# ARDUINO_MSP430F2370.net
KiCad netlist of a schematic drawn in Altium Designer
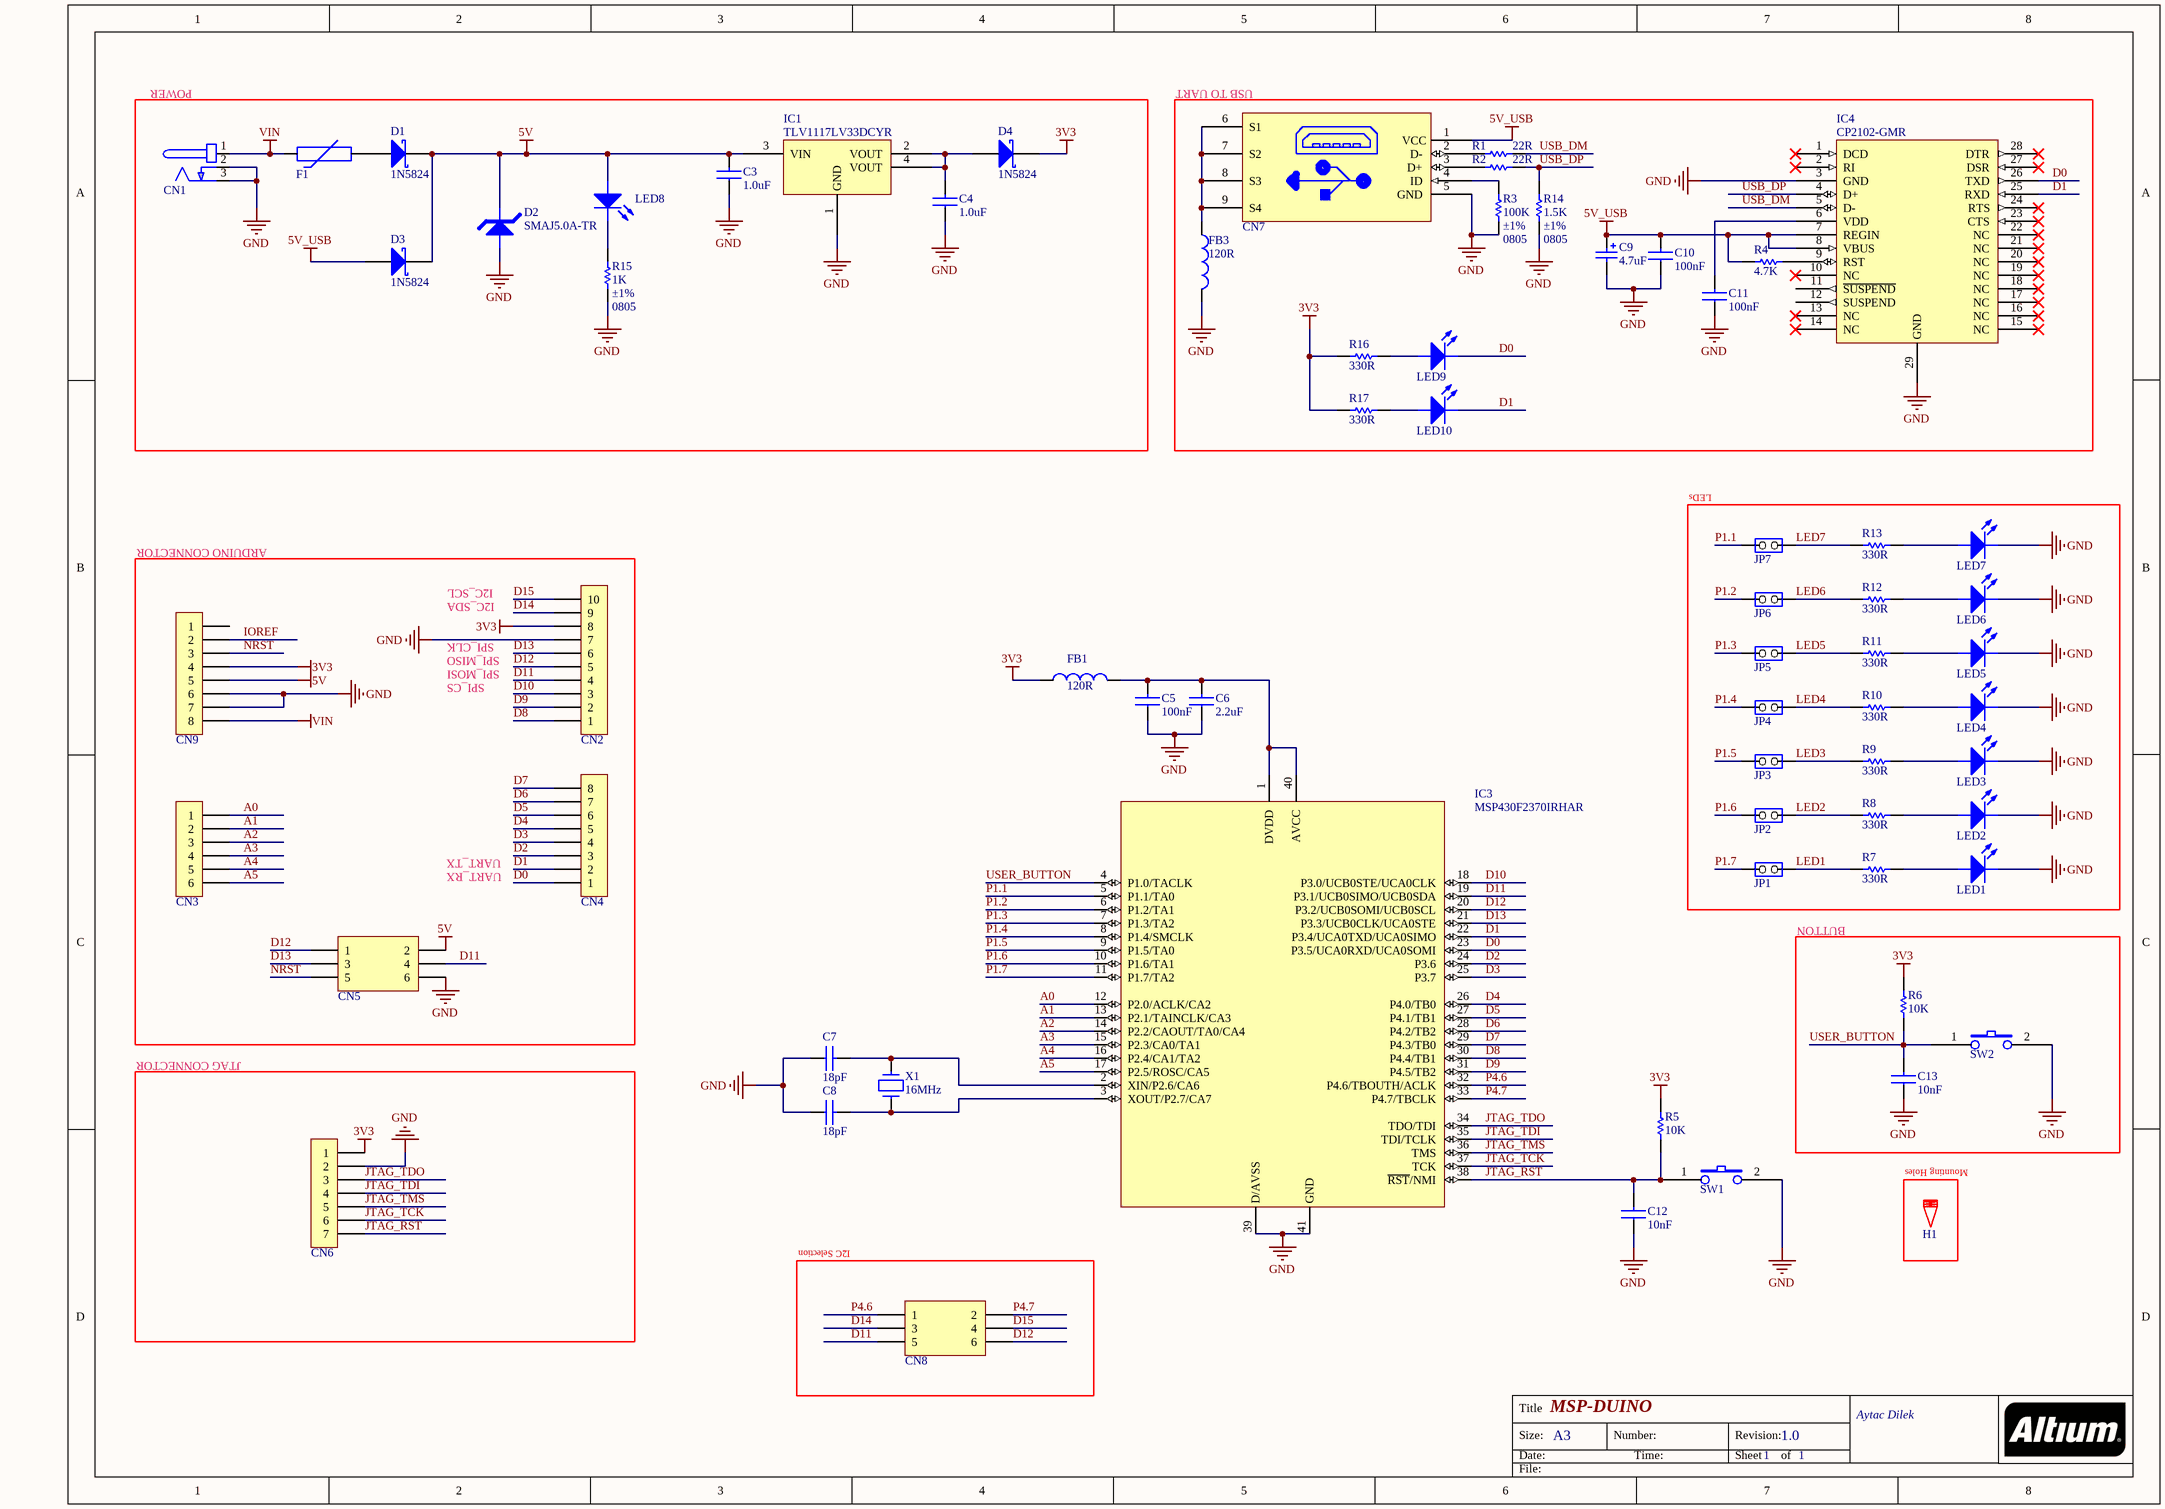
[diagram p0: ARDUINO_MSP430F2370.SchDoc]

(export (version "E")
  (design (tool "Eeschema 10.0.6"))
  (components
    (comp (ref "C3")
      (value "1.0uF")
      (footprint "CAPC2012X100N_EIA0805")
      (description "CAP CER 1UF 25V 10% X7R 0603")
      (fields (field (name "PART NUMBER") "SCAP00310053") (field (name "TOLERANCE") "±10%"))
      (libsource (lib "ComponentDatabase") (part "CAP_NP"))
    )
    (comp (ref "C4")
      (value "1.0uF")
      (footprint "CAPC2012X100N_EIA0805")
      (description "CAP CER 1UF 25V 10% X7R 0603")
      (fields (field (name "PART NUMBER") "SCAP00310053") (field (name "TOLERANCE") "±10%"))
      (libsource (lib "ComponentDatabase") (part "CAP_NP"))
    )
    (comp (ref "C5")
      (value "100nF")
      (footprint "CAPC2012X100N_EIA0805")
      (description "CAP CER 0.1UF 50V 10% X7R 0603")
      (fields (field (name "PART NUMBER") "SCAP00310048") (field (name "TOLERANCE") "±10%"))
      (libsource (lib "ComponentDatabase") (part "CAP_NP"))
    )
    (comp (ref "C6")
      (value "2.2uF")
      (footprint "CAPC2012X100N_EIA0805")
      (description "CAP CER 2.2UF 16V X5R 0805")
      (fields (field (name "PART NUMBER") "SCAP00300098") (field (name "TOLERANCE") "±10%"))
      (libsource (lib "ComponentDatabase") (part "CAP_NP"))
    )
    (comp (ref "C7")
      (value "18pF")
      (footprint "CAPC2012X100N_EIA0805")
      (description "CAP CER 18PF 50V 5% NP0 0603")
      (fields (field (name "PART NUMBER") "SCAP00310014") (field (name "TOLERANCE") "±5%"))
      (libsource (lib "ComponentDatabase") (part "CAP_NP"))
    )
    (comp (ref "C8")
      (value "18pF")
      (footprint "CAPC2012X100N_EIA0805")
      (description "CAP CER 18PF 50V 5% NP0 0603")
      (fields (field (name "PART NUMBER") "SCAP00310014") (field (name "TOLERANCE") "±5%"))
      (libsource (lib "ComponentDatabase") (part "CAP_NP"))
    )
    (comp (ref "C9")
      (value "4.7uF")
      (footprint "CAPMP3216X16N_EIA-1206_CASE-A")
      (description "CAP TANT 4.7UF 16V 10% 1206")
      (fields (field (name "PART NUMBER") "SCAP00367") (field (name "TOLERANCE") "±10%"))
      (libsource (lib "ComponentDatabase") (part "CAP_P"))
    )
    (comp (ref "C10")
      (value "100nF")
      (footprint "CAPC2012X100N_EIA0805")
      (description "CAP CER 0.1UF 50V 10% X7R 0603")
      (fields (field (name "PART NUMBER") "SCAP00310048") (field (name "TOLERANCE") "±10%"))
      (libsource (lib "ComponentDatabase") (part "CAP_NP"))
    )
    (comp (ref "C11")
      (value "100nF")
      (footprint "CAPC2012X100N_EIA0805")
      (description "CAP CER 0.1UF 50V 10% X7R 0603")
      (fields (field (name "PART NUMBER") "SCAP00310048") (field (name "TOLERANCE") "±10%"))
      (libsource (lib "ComponentDatabase") (part "CAP_NP"))
    )
    (comp (ref "C12")
      (value "10nF")
      (footprint "CAPC2012X100N_EIA0805")
      (description "CAP CER 10000PF 50V 10% X7R 0603")
      (fields (field (name "PART NUMBER") "SCAP00310042") (field (name "TOLERANCE") "±10%"))
      (libsource (lib "ComponentDatabase") (part "CAP_NP"))
    )
    (comp (ref "C13")
      (value "10nF")
      (footprint "CAPC2012X100N_EIA0805")
      (description "CAP CER 10000PF 50V 10% X7R 0603")
      (fields (field (name "PART NUMBER") "SCAP00310042") (field (name "TOLERANCE") "±10%"))
      (libsource (lib "ComponentDatabase") (part "CAP_NP"))
    )
    (comp (ref "CN1")
      (value "DC_JACK")
      (footprint "DC_JACK")
      (description "CONN POWER JACK MALE 2.5MM CLSD")
      (fields (field (name "PART NUMBER") "SCON00027") (field (name "VOLTAGE") "24VDC"))
      (libsource (lib "ComponentDatabase") (part "DC_JACK"))
    )
    (comp (ref "CN2")
      (value "HDR_1X10")
      (footprint "HDRFV10W70P254_1X10_2540X254X1118P")
      (description "CONN ARDUINO HEADER .0100\" 10POS")
      (fields (field (name "PART NUMBER") "SCON00126") (field (name "MANUFACTURER") "Sparkfun"))
      (libsource (lib "ComponentDatabase") (part "HDR_1X10"))
    )
    (comp (ref "CN3")
      (value "HDR_1X6")
      (footprint "HDRFV6W70P254_1X6_1524X254X1118P")
      (description "CONN ARDUINO HEADER .0100\" 6POS")
      (fields (field (name "PART NUMBER") "SCON00124") (field (name "MANUFACTURER") "Sparkfun"))
      (libsource (lib "ComponentDatabase") (part "HDR_1X6"))
    )
    (comp (ref "CN4")
      (value "HDR_1X8")
      (footprint "HDRFV8W70P254_1X8_2032X254X1118P")
      (description "CONN ARDUINO HEADER .0100\" 8POS")
      (fields (field (name "PART NUMBER") "SCON00125") (field (name "MANUFACTURER") "Sparkfun"))
      (libsource (lib "") (part "HDR_1X8_1"))
    )
    (comp (ref "CN5")
      (value "HDR_2X3")
      (footprint "HDRV6W64P254_2X3_762X508X600P")
      (description "CONN HEADER FMALE 6PS .1\" DL TIN")
      (fields
        (field (name "PART NUMBER") "SCON00128")
        (field (name "MANUFACTURER") "Sullins Connector Solutions")
      )
      (libsource (lib "ComponentDatabase") (part "HDR_2X3"))
    )
    (comp (ref "CN6")
      (value "HDR_1X7")
      (footprint "HDRFV7W70P254_1X7_1778X254X1118P")
      (description "CONN ARDUINO HEADER .0100\" 7POS")
      (fields (field (name "PART NUMBER") "SCON00129") (field (name "MANUFACTURER") "Wurth Electronics Inc"))
      (libsource (lib "ComponentDatabase") (part "HDR_1X7"))
    )
    (comp (ref "CN7")
      (value "USB_MINI_TYPE_B")
      (footprint "OST_USB-M26FTR")
      (description "CONN USB MINI B R/A SMD")
      (fields (field (name "PART NUMBER") "SCON00017") (field (name "MANUFACTURER") "On Shore Technology"))
      (libsource (lib "ComponentDatabase") (part "USB_MINI_TYPE_B"))
    )
    (comp (ref "CN8")
      (value "HDR_2X3")
      (footprint "HDRV6W64P254_2X3_762X508X600P")
      (description "CONN HEADER FMALE 6PS .1\" DL TIN")
      (fields
        (field (name "PART NUMBER") "SCON00128")
        (field (name "MANUFACTURER") "Sullins Connector Solutions")
      )
      (libsource (lib "ComponentDatabase") (part "HDR_2X3"))
    )
    (comp (ref "CN9")
      (value "HDR_1X8")
      (footprint "HDRFV8W70P254_1X8_2032X254X1118P")
      (description "CONN ARDUINO HEADER .0100\" 8POS")
      (fields (field (name "PART NUMBER") "SCON00125") (field (name "MANUFACTURER") "Sparkfun"))
      (libsource (lib "ComponentDatabase") (part "HDR_1X8"))
    )
    (comp (ref "D1")
      (value "1N5824")
      (footprint "DIOM4436X24N_DO-214AA_SMB")
      (description "DIODE SCHOTTKY 5A 40V SMA")
      (fields (field (name "PART NUMBER") "SSEM00019") (field (name "MANUFACTURER") "Micro Commercial Co"))
      (libsource (lib "ComponentDatabase") (part "DIODE_SCHOTTKY"))
    )
    (comp (ref "D2")
      (value "SMAJ5.0A-TR")
      (footprint "DIOM5126X26N_DO-214AC_SMA")
      (description "TVS DIODE 5VWM 13.4VC DO214AC")
      (fields (field (name "PART NUMBER") "SCP00004") (field (name "MANUFACTURER") "STMicroelectronics"))
      (libsource (lib "ComponentDatabase") (part "DIODE_TVS_UNI"))
    )
    (comp (ref "D3")
      (value "1N5824")
      (footprint "DIOM4436X24N_DO-214AA_SMB")
      (description "DIODE SCHOTTKY 5A 40V SMA")
      (fields (field (name "PART NUMBER") "SSEM00019") (field (name "MANUFACTURER") "Micro Commercial Co"))
      (libsource (lib "ComponentDatabase") (part "DIODE_SCHOTTKY"))
    )
    (comp (ref "D4")
      (value "1N5824")
      (footprint "DIOM4436X24N_DO-214AA_SMB")
      (description "DIODE SCHOTTKY 5A 40V SMA")
      (fields (field (name "PART NUMBER") "SSEM00019") (field (name "MANUFACTURER") "Micro Commercial Co"))
      (libsource (lib "ComponentDatabase") (part "DIODE_SCHOTTKY"))
    )
    (comp (ref "F1")
      (value "PTC")
      (footprint "FUSEC2012X18N")
      (description "PTC RESTTBLE 1.0A 6V CHIP 0805")
      (fields (field (name "PART NUMBER") "SCP00003") (field (name "MANUFACTURER") "Bel Fuse Inc."))
      (libsource (lib "ComponentDatabase") (part "PTC"))
    )
    (comp (ref "FB1")
      (value "BEAD")
      (footprint "FILC2012X100N_EIA0805")
      (description "FERRITE CHIP POWER 120 OHM SMD")
      (fields
        (field (name "PART NUMBER") "SFIL00005")
        (field (name "IMPEDANCE") "120R")
        (field (name "MANUFACTURER") "Laird-Signal Integrity Products")
      )
      (libsource (lib "ComponentDatabase") (part "BEAD"))
    )
    (comp (ref "FB3")
      (value "BEAD")
      (footprint "FILC2012X100N_EIA0805")
      (description "FERRITE CHIP POWER 120 OHM SMD")
      (fields
        (field (name "PART NUMBER") "SFIL00005")
        (field (name "IMPEDANCE") "120R")
        (field (name "MANUFACTURER") "Laird-Signal Integrity Products")
      )
      (libsource (lib "ComponentDatabase") (part "BEAD"))
    )
    (comp (ref "H1")
      (value "HOLES")
      (footprint "HOLE_125MIL")
      (description "Holes")
      (fields (field (name "PART NUMBER") "SMSC00005"))
      (libsource (lib "ComponentDatabase") (part "HOLES"))
    )
    (comp (ref "IC1")
      (value "TLV1117LV33DCYR")
      (footprint "SOT230P700X180-4N_[TEXAS]R-PDSO-G4")
      (description "IC REG LDO 3.3V 1A SOT223")
      (fields
        (field (name "PART NUMBER") "SIC00137")
        (field (name "MANUFACTURER PART NUMBER") "TLV1117LV33DCYR")
        (field (name "MANUFACTURER") "Texas Instruments")
      )
      (libsource (lib "ComponentDatabase") (part "TLV1117LV33DCYR"))
    )
    (comp (ref "IC3")
      (value "MSP430F2370")
      (footprint "QFN50P600X600X100_HS-41N")
      (description "IC MCU 16BIT 32KB FLASH 40VQFN")
      (fields
        (field (name "PART NUMBER") "SIC00129")
        (field (name "MANUFACTURER PART NUMBER") "MSP430F2370IRHAR")
        (field (name "MANUFACTURER") "Texas Instruments")
      )
      (libsource (lib "ComponentDatabase") (part "MSP430F2370"))
    )
    (comp (ref "IC4")
      (value "CP2102")
      (footprint "QFN50P500X500X100_HS-29N")
      (description "IC USB-TO-UART BRIDGE 28VQFN")
      (fields
        (field (name "PART NUMBER") "SIC00136")
        (field (name "MANUFACTURER PART NUMBER") "CP2102-GMR")
        (field (name "MANUFACTURER") "Silicon Labs")
      )
      (libsource (lib "ComponentDatabase") (part "CP2102"))
    )
    (comp (ref "JP1")
      (value "JP2")
      (footprint "HDRV2W64P254_1X2_508X254X600P")
      (description "SIL VERTICAL PC TAIL PIN HEADER")
      (fields (field (name "PART NUMBER") "SCON00130") (field (name "MANUFACTURER") "Harwin Inc."))
      (libsource (lib "ComponentDatabase") (part "JP2"))
    )
    (comp (ref "JP2")
      (value "JP2")
      (footprint "HDRV2W64P254_1X2_508X254X600P")
      (description "SIL VERTICAL PC TAIL PIN HEADER")
      (fields (field (name "PART NUMBER") "SCON00130") (field (name "MANUFACTURER") "Harwin Inc."))
      (libsource (lib "ComponentDatabase") (part "JP2"))
    )
    (comp (ref "JP3")
      (value "JP2")
      (footprint "HDRV2W64P254_1X2_508X254X600P")
      (description "SIL VERTICAL PC TAIL PIN HEADER")
      (fields (field (name "PART NUMBER") "SCON00130") (field (name "MANUFACTURER") "Harwin Inc."))
      (libsource (lib "ComponentDatabase") (part "JP2"))
    )
    (comp (ref "JP4")
      (value "JP2")
      (footprint "HDRV2W64P254_1X2_508X254X600P")
      (description "SIL VERTICAL PC TAIL PIN HEADER")
      (fields (field (name "PART NUMBER") "SCON00130") (field (name "MANUFACTURER") "Harwin Inc."))
      (libsource (lib "ComponentDatabase") (part "JP2"))
    )
    (comp (ref "JP5")
      (value "JP2")
      (footprint "HDRV2W64P254_1X2_508X254X600P")
      (description "SIL VERTICAL PC TAIL PIN HEADER")
      (fields (field (name "PART NUMBER") "SCON00130") (field (name "MANUFACTURER") "Harwin Inc."))
      (libsource (lib "ComponentDatabase") (part "JP2"))
    )
    (comp (ref "JP6")
      (value "JP2")
      (footprint "HDRV2W64P254_1X2_508X254X600P")
      (description "SIL VERTICAL PC TAIL PIN HEADER")
      (fields (field (name "PART NUMBER") "SCON00130") (field (name "MANUFACTURER") "Harwin Inc."))
      (libsource (lib "ComponentDatabase") (part "JP2"))
    )
    (comp (ref "JP7")
      (value "JP2")
      (footprint "HDRV2W64P254_1X2_508X254X600P")
      (description "SIL VERTICAL PC TAIL PIN HEADER")
      (fields (field (name "PART NUMBER") "SCON00130") (field (name "MANUFACTURER") "Harwin Inc."))
      (libsource (lib "ComponentDatabase") (part "JP2"))
    )
    (comp (ref "LED1")
      (value "LED")
      (footprint "LEDC2012X70N_EIA0805_BLUE")
      (description "LED BLUE CLEAR 0805 SMD")
      (fields (field (name "PART NUMBER") "SOPT00001") (field (name "MANUFACTURER") "Lite-On Inc"))
      (libsource (lib "ComponentDatabase") (part "LED"))
    )
    (comp (ref "LED2")
      (value "LED")
      (footprint "LEDC2012X70N_EIA0805_ORANGE")
      (description "LED ORANGE CLEAR 0805 SMD")
      (fields (field (name "PART NUMBER") "SOPT00003") (field (name "MANUFACTURER") "Lite-On Inc"))
      (libsource (lib "ComponentDatabase") (part "LED"))
    )
    (comp (ref "LED3")
      (value "LED")
      (footprint "LEDC2012X70N_EIA0805_RED")
      (description "LED SUPER RED CLR THIN 0805 SMD")
      (fields (field (name "PART NUMBER") "SOPT00004") (field (name "MANUFACTURER") "Lite-On Inc"))
      (libsource (lib "ComponentDatabase") (part "LED"))
    )
    (comp (ref "LED4")
      (value "LED")
      (footprint "LEDC2012X70N_EIA0805_WHITE")
      (description "LED WHITE YELLOW 280MCD 0805")
      (fields (field (name "PART NUMBER") "SOPT00005") (field (name "MANUFACTURER") "Lite-On Inc"))
      (libsource (lib "ComponentDatabase") (part "LED"))
    )
    (comp (ref "LED5")
      (value "LED")
      (footprint "LEDC2012X70N_EIA0805_YELLOW")
      (description "LED YELLOW CLEAR RT ANG 0805")
      (fields (field (name "PART NUMBER") "SOPT00006") (field (name "MANUFACTURER") "Lite-On Inc"))
      (libsource (lib "ComponentDatabase") (part "LED"))
    )
    (comp (ref "LED6")
      (value "LED")
      (footprint "LEDC2012X70N_EIA0805_GREEN")
      (description "LED GREEN CLEAR THIN 0805 SMD")
      (fields (field (name "PART NUMBER") "SOPT00002") (field (name "MANUFACTURER") "Lite-On Inc"))
      (libsource (lib "ComponentDatabase") (part "LED"))
    )
    (comp (ref "LED7")
      (value "LED")
      (footprint "LEDC2012X70N_EIA0805_GREEN")
      (description "LED GREEN CLEAR THIN 0805 SMD")
      (fields (field (name "PART NUMBER") "SOPT00002") (field (name "MANUFACTURER") "Lite-On Inc"))
      (libsource (lib "ComponentDatabase") (part "LED"))
    )
    (comp (ref "LED8")
      (value "LED")
      (footprint "LEDC2012X70N_EIA0805_GREEN")
      (description "LED GREEN CLEAR THIN 0805 SMD")
      (fields (field (name "PART NUMBER") "SOPT00002") (field (name "MANUFACTURER") "Lite-On Inc"))
      (libsource (lib "ComponentDatabase") (part "LED"))
    )
    (comp (ref "LED9")
      (value "LED")
      (footprint "LEDC2012X70N_EIA0805_BLUE")
      (description "LED BLUE CLEAR 0805 SMD")
      (fields (field (name "PART NUMBER") "SOPT00001") (field (name "MANUFACTURER") "Lite-On Inc"))
      (libsource (lib "ComponentDatabase") (part "LED"))
    )
    (comp (ref "LED10")
      (value "LED")
      (footprint "LEDC2012X70N_EIA0805_RED")
      (description "LED SUPER RED CLR THIN 0805 SMD")
      (fields (field (name "PART NUMBER") "SOPT00004") (field (name "MANUFACTURER") "Lite-On Inc"))
      (libsource (lib "ComponentDatabase") (part "LED"))
    )
    (comp (ref "R1")
      (value "22R")
      (footprint "RESC2013X65N_EIA0805")
      (description "RES SMD 22 OHM 1% 1/8W 0805")
      (fields (field (name "PART NUMBER") "SRES03010034") (field (name "TOLERANCE") "±1%"))
      (libsource (lib "ComponentDatabase") (part "RES"))
    )
    (comp (ref "R2")
      (value "22R")
      (footprint "RESC2013X65N_EIA0805")
      (description "RES SMD 22 OHM 1% 1/8W 0805")
      (fields (field (name "PART NUMBER") "SRES03010034") (field (name "TOLERANCE") "±1%"))
      (libsource (lib "ComponentDatabase") (part "RES"))
    )
    (comp (ref "R3")
      (value "100K")
      (footprint "RESC2013X65N_EIA0805")
      (description "RES SMD 100K OHM 1% 1/8W 0805")
      (fields
        (field (name "PART NUMBER") "SRES03010122")
        (field (name "TOLERANCE") "±1%")
        (field (name "PACKAGE / CASE") "0805")
        (field (name "MANUFACTURER") "Yageo")
      )
      (libsource (lib "ComponentDatabase") (part "RES"))
    )
    (comp (ref "R4")
      (value "4.7K")
      (footprint "RESC2013X65N_EIA0805")
      (description "RES SMD 4.7K OHM 1% 1/8W 0805")
      (fields (field (name "PART NUMBER") "SRES03010090") (field (name "TOLERANCE") "±1%"))
      (libsource (lib "ComponentDatabase") (part "RES"))
    )
    (comp (ref "R5")
      (value "10K")
      (footprint "RESC2013X65N_EIA0805")
      (description "RES SMD 10K OHM 1% 1/8W 0805")
      (fields (field (name "PART NUMBER") "SRES03010098") (field (name "TOLERANCE") "±1%"))
      (libsource (lib "ComponentDatabase") (part "RES"))
    )
    (comp (ref "R6")
      (value "10K")
      (footprint "RESC2013X65N_EIA0805")
      (description "RES SMD 10K OHM 1% 1/8W 0805")
      (fields (field (name "PART NUMBER") "SRES03010098") (field (name "TOLERANCE") "±1%"))
      (libsource (lib "ComponentDatabase") (part "RES"))
    )
    (comp (ref "R7")
      (value "330R")
      (footprint "RESC2013X65N_EIA0805")
      (description "RES SMD 330 OHM 1% 1/8W 0805")
      (fields (field (name "PART NUMBER") "SRES03010062") (field (name "TOLERANCE") "±1%"))
      (libsource (lib "ComponentDatabase") (part "RES"))
    )
    (comp (ref "R8")
      (value "330R")
      (footprint "RESC2013X65N_EIA0805")
      (description "RES SMD 330 OHM 1% 1/8W 0805")
      (fields (field (name "PART NUMBER") "SRES03010062") (field (name "TOLERANCE") "±1%"))
      (libsource (lib "ComponentDatabase") (part "RES"))
    )
    (comp (ref "R9")
      (value "330R")
      (footprint "RESC2013X65N_EIA0805")
      (description "RES SMD 330 OHM 1% 1/8W 0805")
      (fields (field (name "PART NUMBER") "SRES03010062") (field (name "TOLERANCE") "±1%"))
      (libsource (lib "ComponentDatabase") (part "RES"))
    )
    (comp (ref "R10")
      (value "330R")
      (footprint "RESC2013X65N_EIA0805")
      (description "RES SMD 330 OHM 1% 1/8W 0805")
      (fields (field (name "PART NUMBER") "SRES03010062") (field (name "TOLERANCE") "±1%"))
      (libsource (lib "ComponentDatabase") (part "RES"))
    )
    (comp (ref "R11")
      (value "330R")
      (footprint "RESC2013X65N_EIA0805")
      (description "RES SMD 330 OHM 1% 1/8W 0805")
      (fields (field (name "PART NUMBER") "SRES03010062") (field (name "TOLERANCE") "±1%"))
      (libsource (lib "ComponentDatabase") (part "RES"))
    )
    (comp (ref "R12")
      (value "330R")
      (footprint "RESC2013X65N_EIA0805")
      (description "RES SMD 330 OHM 1% 1/8W 0805")
      (fields (field (name "PART NUMBER") "SRES03010062") (field (name "TOLERANCE") "±1%"))
      (libsource (lib "ComponentDatabase") (part "RES"))
    )
    (comp (ref "R13")
      (value "330R")
      (footprint "RESC2013X65N_EIA0805")
      (description "RES SMD 330 OHM 1% 1/8W 0805")
      (fields (field (name "PART NUMBER") "SRES03010062") (field (name "TOLERANCE") "±1%"))
      (libsource (lib "ComponentDatabase") (part "RES"))
    )
    (comp (ref "R14")
      (value "1.5K")
      (footprint "RESC2013X65N_EIA0805")
      (description "RES SMD 1.5K OHM 1% 1/8W 0805")
      (fields
        (field (name "PART NUMBER") "SRES03010078")
        (field (name "TOLERANCE") "±1%")
        (field (name "PACKAGE / CASE") "0805")
        (field (name "MANUFACTURER") "Yageo")
      )
      (libsource (lib "ComponentDatabase") (part "RES"))
    )
    (comp (ref "R15")
      (value "1K")
      (footprint "RESC2013X65N_EIA0805")
      (description "RES SMD 1K OHM 1% 1/8W 0805")
      (fields
        (field (name "PART NUMBER") "SRES03010074")
        (field (name "TOLERANCE") "±1%")
        (field (name "PACKAGE / CASE") "0805")
        (field (name "MANUFACTURER") "Yageo")
      )
      (libsource (lib "ComponentDatabase") (part "RES"))
    )
    (comp (ref "R16")
      (value "330R")
      (footprint "RESC2013X65N_EIA0805")
      (description "RES SMD 330 OHM 1% 1/8W 0805")
      (fields (field (name "PART NUMBER") "SRES03010062") (field (name "TOLERANCE") "±1%"))
      (libsource (lib "ComponentDatabase") (part "RES"))
    )
    (comp (ref "R17")
      (value "330R")
      (footprint "RESC2013X65N_EIA0805")
      (description "RES SMD 330 OHM 1% 1/8W 0805")
      (fields (field (name "PART NUMBER") "SRES03010062") (field (name "TOLERANCE") "±1%"))
      (libsource (lib "ComponentDatabase") (part "RES"))
    )
    (comp (ref "SW1")
      (value "SWITCH_TACTILE_2PIN")
      (footprint "[C&K]RS-282G05A3-SM_RT")
      (description "SWITCH TACTILE SPST-NO 0.05A 12V")
      (fields (field (name "PART NUMBER") "SSWI00022") (field (name "VOLTAGE") "12VDC"))
      (libsource (lib "ComponentDatabase") (part "SWITCH_TACTILE_2PIN"))
    )
    (comp (ref "SW2")
      (value "SWITCH_TACTILE_2PIN")
      (footprint "[C&K]RS-282G05A3-SM_RT")
      (description "SWITCH TACTILE SPST-NO 0.05A 12V")
      (fields (field (name "PART NUMBER") "SSWI00022") (field (name "VOLTAGE") "12VDC"))
      (libsource (lib "ComponentDatabase") (part "SWITCH_TACTILE_2PIN"))
    )
    (comp (ref "X1")
      (value "16MHz")
      (footprint "HC-49/US")
      (description "CRYSTAL 16.0000MHZ 20PF T/H")
      (fields (field (name "PART NUMBER") "SCRY00011") (field (name "MANUFACTURER") "CTS-Frequency Controls"))
      (libsource (lib "ComponentDatabase") (part "CRYSTAL"))
    )
  )
  (nets
    (net (code "1") (name "/A0") (class "Default")
      (node (ref "CN3") (pin "1") (pinfunction "1_1") (pintype "passive"))
      (node (ref "IC3") (pin "12") (pinfunction "P2.0/ACLK/CA2_12") (pintype "bidirectional"))
    )
    (net (code "2") (name "/A1") (class "Default")
      (node (ref "CN3") (pin "2") (pinfunction "2_2") (pintype "passive"))
      (node (ref "IC3") (pin "13") (pinfunction "P2.1/TAINCLK/CA3_13") (pintype "bidirectional"))
    )
    (net (code "3") (name "/A2") (class "Default")
      (node (ref "CN3") (pin "3") (pinfunction "3_3") (pintype "passive"))
      (node (ref "IC3") (pin "14") (pinfunction "P2.2/CAOUT/TA0/CA4_14") (pintype "bidirectional"))
    )
    (net (code "4") (name "/A3") (class "Default")
      (node (ref "CN3") (pin "4") (pinfunction "4_4") (pintype "passive"))
      (node (ref "IC3") (pin "15") (pinfunction "P2.3/CA0/TA1_15") (pintype "bidirectional"))
    )
    (net (code "5") (name "/A4") (class "Default")
      (node (ref "CN3") (pin "5") (pinfunction "5_5") (pintype "passive"))
      (node (ref "IC3") (pin "16") (pinfunction "P2.4/CA1/TA2_16") (pintype "bidirectional"))
    )
    (net (code "6") (name "/A5") (class "Default")
      (node (ref "CN3") (pin "6") (pinfunction "6_6") (pintype "passive"))
      (node (ref "IC3") (pin "17") (pinfunction "P2.5/ROSC/CA5_17") (pintype "bidirectional"))
    )
    (net (code "7") (name "/D0") (class "Default")
      (node (ref "CN4") (pin "1") (pinfunction "1_1") (pintype "passive"))
      (node (ref "IC3") (pin "23") (pinfunction "P3.5/UCA0RXD/UCA0SOMI_23") (pintype "bidirectional"))
      (node (ref "IC4") (pin "26") (pinfunction "TXD_26") (pintype "output"))
      (node (ref "LED9") (pin "1") (pinfunction "1_1") (pintype "passive"))
    )
    (net (code "8") (name "/D1") (class "Default")
      (node (ref "CN4") (pin "2") (pinfunction "2_2") (pintype "passive"))
      (node (ref "IC3") (pin "22") (pinfunction "P3.4/UCA0TXD/UCA0SIMO_22") (pintype "bidirectional"))
      (node (ref "IC4") (pin "25") (pinfunction "RXD_25") (pintype "input"))
      (node (ref "LED10") (pin "1") (pinfunction "1_1") (pintype "passive"))
    )
    (net (code "9") (name "/D2") (class "Default")
      (node (ref "CN4") (pin "3") (pinfunction "3_3") (pintype "passive"))
      (node (ref "IC3") (pin "24") (pinfunction "P3.6_24") (pintype "bidirectional"))
    )
    (net (code "10") (name "/D3") (class "Default")
      (node (ref "CN4") (pin "4") (pinfunction "4_4") (pintype "passive"))
      (node (ref "IC3") (pin "25") (pinfunction "P3.7_25") (pintype "bidirectional"))
    )
    (net (code "11") (name "/D4") (class "Default")
      (node (ref "CN4") (pin "5") (pinfunction "5_5") (pintype "passive"))
      (node (ref "IC3") (pin "26") (pinfunction "P4.0/TB0_26") (pintype "bidirectional"))
    )
    (net (code "12") (name "/D5") (class "Default")
      (node (ref "CN4") (pin "6") (pinfunction "6_6") (pintype "passive"))
      (node (ref "IC3") (pin "27") (pinfunction "P4.1/TB1_27") (pintype "bidirectional"))
    )
    (net (code "13") (name "/D6") (class "Default")
      (node (ref "CN4") (pin "7") (pinfunction "7_7") (pintype "passive"))
      (node (ref "IC3") (pin "28") (pinfunction "P4.2/TB2_28") (pintype "bidirectional"))
    )
    (net (code "14") (name "/D7") (class "Default")
      (node (ref "CN4") (pin "8") (pinfunction "8_8") (pintype "passive"))
      (node (ref "IC3") (pin "29") (pinfunction "P4.3/TB0_29") (pintype "bidirectional"))
    )
    (net (code "15") (name "/D8") (class "Default")
      (node (ref "CN2") (pin "1") (pinfunction "1_1") (pintype "passive"))
      (node (ref "IC3") (pin "30") (pinfunction "P4.4/TB1_30") (pintype "bidirectional"))
    )
    (net (code "16") (name "/D9") (class "Default")
      (node (ref "CN2") (pin "2") (pinfunction "2_2") (pintype "passive"))
      (node (ref "IC3") (pin "31") (pinfunction "P4.5/TB2_31") (pintype "bidirectional"))
    )
    (net (code "17") (name "/D10") (class "Default")
      (node (ref "CN2") (pin "3") (pinfunction "3_3") (pintype "passive"))
      (node (ref "IC3") (pin "18") (pinfunction "P3.0/UCB0STE/UCA0CLK_18") (pintype "bidirectional"))
    )
    (net (code "18") (name "/D11") (class "Default")
      (node (ref "CN2") (pin "4") (pinfunction "4_4") (pintype "passive"))
      (node (ref "CN5") (pin "4") (pinfunction "4_4") (pintype "passive"))
      (node (ref "CN8") (pin "5") (pinfunction "5_5") (pintype "passive"))
      (node (ref "IC3") (pin "19") (pinfunction "P3.1/UCB0SIMO/UCB0SDA_19") (pintype "bidirectional"))
    )
    (net (code "19") (name "/D12") (class "Default")
      (node (ref "CN2") (pin "5") (pinfunction "5_5") (pintype "passive"))
      (node (ref "CN5") (pin "1") (pinfunction "1_1") (pintype "passive"))
      (node (ref "CN8") (pin "6") (pinfunction "6_6") (pintype "passive"))
      (node (ref "IC3") (pin "20") (pinfunction "P3.2/UCB0SOMI/UCB0SCL_20") (pintype "bidirectional"))
    )
    (net (code "20") (name "/D13") (class "Default")
      (node (ref "CN2") (pin "6") (pinfunction "6_6") (pintype "passive"))
      (node (ref "CN5") (pin "3") (pinfunction "3_3") (pintype "passive"))
      (node (ref "IC3") (pin "21") (pinfunction "P3.3/UCB0CLK/UCA0STE_21") (pintype "bidirectional"))
    )
    (net (code "21") (name "/D14") (class "Default")
      (node (ref "CN2") (pin "9") (pinfunction "9_9") (pintype "passive"))
      (node (ref "CN8") (pin "3") (pinfunction "3_3") (pintype "passive"))
    )
    (net (code "22") (name "/D15") (class "Default")
      (node (ref "CN2") (pin "10") (pinfunction "10_10") (pintype "passive"))
      (node (ref "CN8") (pin "4") (pinfunction "4_4") (pintype "passive"))
    )
    (net (code "23") (name "/IOREF") (class "Default")
      (node (ref "CN9") (pin "2") (pinfunction "2_2") (pintype "passive"))
    )
    (net (code "24") (name "/JTAG_RST") (class "Default")
      (node (ref "C12") (pin "2") (pinfunction "2_2") (pintype "passive"))
      (node (ref "CN6") (pin "7") (pinfunction "7_7") (pintype "passive"))
      (node (ref "IC3") (pin "38") (pinfunction "~{RST}/NMI_38") (pintype "bidirectional"))
      (node (ref "R5") (pin "2") (pinfunction "2_2") (pintype "passive"))
      (node (ref "SW1") (pin "1") (pinfunction "A0_1") (pintype "passive"))
    )
    (net (code "25") (name "/JTAG_TCK") (class "Default")
      (node (ref "CN6") (pin "6") (pinfunction "6_6") (pintype "passive"))
      (node (ref "IC3") (pin "37") (pinfunction "TCK_37") (pintype "bidirectional"))
    )
    (net (code "26") (name "/JTAG_TDI") (class "Default")
      (node (ref "CN6") (pin "4") (pinfunction "4_4") (pintype "passive"))
      (node (ref "IC3") (pin "35") (pinfunction "TDI/TCLK_35") (pintype "bidirectional"))
    )
    (net (code "27") (name "/JTAG_TDO") (class "Default")
      (node (ref "CN6") (pin "3") (pinfunction "3_3") (pintype "passive"))
      (node (ref "IC3") (pin "34") (pinfunction "TDO/TDI_34") (pintype "bidirectional"))
    )
    (net (code "28") (name "/JTAG_TMS") (class "Default")
      (node (ref "CN6") (pin "5") (pinfunction "5_5") (pintype "passive"))
      (node (ref "IC3") (pin "36") (pinfunction "TMS_36") (pintype "bidirectional"))
    )
    (net (code "29") (name "/LED1") (class "Default")
      (node (ref "JP1") (pin "2") (pinfunction "NO_2") (pintype "passive"))
      (node (ref "R7") (pin "2") (pinfunction "2_2") (pintype "passive"))
    )
    (net (code "30") (name "/LED2") (class "Default")
      (node (ref "JP2") (pin "2") (pinfunction "NO_2") (pintype "passive"))
      (node (ref "R8") (pin "2") (pinfunction "2_2") (pintype "passive"))
    )
    (net (code "31") (name "/LED3") (class "Default")
      (node (ref "JP3") (pin "2") (pinfunction "NO_2") (pintype "passive"))
      (node (ref "R9") (pin "2") (pinfunction "2_2") (pintype "passive"))
    )
    (net (code "32") (name "/LED4") (class "Default")
      (node (ref "JP4") (pin "2") (pinfunction "NO_2") (pintype "passive"))
      (node (ref "R10") (pin "2") (pinfunction "2_2") (pintype "passive"))
    )
    (net (code "33") (name "/LED5") (class "Default")
      (node (ref "JP5") (pin "2") (pinfunction "NO_2") (pintype "passive"))
      (node (ref "R11") (pin "2") (pinfunction "2_2") (pintype "passive"))
    )
    (net (code "34") (name "/LED6") (class "Default")
      (node (ref "JP6") (pin "2") (pinfunction "NO_2") (pintype "passive"))
      (node (ref "R12") (pin "2") (pinfunction "2_2") (pintype "passive"))
    )
    (net (code "35") (name "/LED7") (class "Default")
      (node (ref "JP7") (pin "2") (pinfunction "NO_2") (pintype "passive"))
      (node (ref "R13") (pin "2") (pinfunction "2_2") (pintype "passive"))
    )
    (net (code "36") (name "/P1.1") (class "Default")
      (node (ref "IC3") (pin "5") (pinfunction "P1.1/TA0_5") (pintype "bidirectional"))
      (node (ref "JP7") (pin "1") (pinfunction "COMMON_1") (pintype "passive"))
    )
    (net (code "37") (name "/P1.2") (class "Default")
      (node (ref "IC3") (pin "6") (pinfunction "P1.2/TA1_6") (pintype "bidirectional"))
      (node (ref "JP6") (pin "1") (pinfunction "COMMON_1") (pintype "passive"))
    )
    (net (code "38") (name "/P1.3") (class "Default")
      (node (ref "IC3") (pin "7") (pinfunction "P1.3/TA2_7") (pintype "bidirectional"))
      (node (ref "JP5") (pin "1") (pinfunction "COMMON_1") (pintype "passive"))
    )
    (net (code "39") (name "/P1.4") (class "Default")
      (node (ref "IC3") (pin "8") (pinfunction "P1.4/SMCLK_8") (pintype "bidirectional"))
      (node (ref "JP4") (pin "1") (pinfunction "COMMON_1") (pintype "passive"))
    )
    (net (code "40") (name "/P1.5") (class "Default")
      (node (ref "IC3") (pin "9") (pinfunction "P1.5/TA0_9") (pintype "bidirectional"))
      (node (ref "JP3") (pin "1") (pinfunction "COMMON_1") (pintype "passive"))
    )
    (net (code "41") (name "/P1.6") (class "Default")
      (node (ref "IC3") (pin "10") (pinfunction "P1.6/TA1_10") (pintype "bidirectional"))
      (node (ref "JP2") (pin "1") (pinfunction "COMMON_1") (pintype "passive"))
    )
    (net (code "42") (name "/P1.7") (class "Default")
      (node (ref "IC3") (pin "11") (pinfunction "P1.7/TA2_11") (pintype "bidirectional"))
      (node (ref "JP1") (pin "1") (pinfunction "COMMON_1") (pintype "passive"))
    )
    (net (code "43") (name "/P4.6") (class "Default")
      (node (ref "CN8") (pin "1") (pinfunction "1_1") (pintype "passive"))
      (node (ref "IC3") (pin "32") (pinfunction "P4.6/TBOUTH/ACLK_32") (pintype "bidirectional"))
    )
    (net (code "44") (name "/P4.7") (class "Default")
      (node (ref "CN8") (pin "2") (pinfunction "2_2") (pintype "passive"))
      (node (ref "IC3") (pin "33") (pinfunction "P4.7/TBCLK_33") (pintype "bidirectional"))
    )
    (net (code "45") (name "/USB_DM") (class "Default")
      (node (ref "IC4") (pin "5") (pinfunction "D-_5") (pintype "bidirectional"))
      (node (ref "R1") (pin "1") (pinfunction "1_1") (pintype "passive"))
    )
    (net (code "46") (name "/USB_DP") (class "Default")
      (node (ref "IC4") (pin "4") (pinfunction "D+_4") (pintype "bidirectional"))
      (node (ref "R14") (pin "1") (pinfunction "1_1") (pintype "passive"))
      (node (ref "R2") (pin "1") (pinfunction "1_1") (pintype "passive"))
    )
    (net (code "47") (name "/USER_BUTTON") (class "Default")
      (node (ref "C13") (pin "2") (pinfunction "2_2") (pintype "passive"))
      (node (ref "IC3") (pin "4") (pinfunction "P1.0/TACLK_4") (pintype "bidirectional"))
      (node (ref "R6") (pin "2") (pinfunction "2_2") (pintype "passive"))
      (node (ref "SW2") (pin "1") (pinfunction "A0_1") (pintype "passive"))
    )
    (net (code "48") (name "/~{NRST}") (class "Default")
      (node (ref "CN5") (pin "5") (pinfunction "5_5") (pintype "passive"))
      (node (ref "CN9") (pin "3") (pinfunction "3_3") (pintype "passive"))
    )
    (net (code "49") (name "3V3") (class "Default")
      (node (ref "CN2") (pin "8") (pinfunction "8_8") (pintype "passive"))
      (node (ref "CN6") (pin "1") (pinfunction "1_1") (pintype "passive"))
      (node (ref "CN9") (pin "4") (pinfunction "4_4") (pintype "passive"))
      (node (ref "D4") (pin "1") (pinfunction "1_1") (pintype "passive"))
      (node (ref "FB1") (pin "1") (pinfunction "1_1") (pintype "passive"))
      (node (ref "R16") (pin "2") (pinfunction "2_2") (pintype "passive"))
      (node (ref "R17") (pin "2") (pinfunction "2_2") (pintype "passive"))
      (node (ref "R5") (pin "1") (pinfunction "1_1") (pintype "passive"))
      (node (ref "R6") (pin "1") (pinfunction "1_1") (pintype "passive"))
    )
    (net (code "50") (name "5V") (class "Default")
      (node (ref "C3") (pin "2") (pinfunction "2_2") (pintype "passive"))
      (node (ref "CN5") (pin "2") (pinfunction "2_2") (pintype "passive"))
      (node (ref "CN9") (pin "5") (pinfunction "5_5") (pintype "passive"))
      (node (ref "D1") (pin "1") (pinfunction "1_1") (pintype "passive"))
      (node (ref "D2") (pin "1") (pinfunction "1_1") (pintype "passive"))
      (node (ref "D3") (pin "1") (pinfunction "1_1") (pintype "passive"))
      (node (ref "IC1") (pin "3") (pinfunction "VIN_3") (pintype "passive"))
      (node (ref "LED8") (pin "2") (pinfunction "2_2") (pintype "passive"))
    )
    (net (code "51") (name "5V_USB") (class "Default")
      (node (ref "C10") (pin "2") (pinfunction "2_2") (pintype "passive"))
      (node (ref "C9") (pin "1") (pinfunction "1_1") (pintype "passive"))
      (node (ref "CN7") (pin "1") (pinfunction "VCC_1") (pintype "power_in"))
      (node (ref "D3") (pin "2") (pinfunction "2_2") (pintype "passive"))
      (node (ref "IC4") (pin "7") (pinfunction "REGIN_7") (pintype "power_in"))
      (node (ref "IC4") (pin "8") (pinfunction "VBUS_8") (pintype "input"))
      (node (ref "R4") (pin "2") (pinfunction "2_2") (pintype "passive"))
    )
    (net (code "52") (name "GND") (class "Default")
      (node (ref "C10") (pin "1") (pinfunction "1_1") (pintype "passive"))
      (node (ref "C11") (pin "1") (pinfunction "1_1") (pintype "passive"))
      (node (ref "C12") (pin "1") (pinfunction "1_1") (pintype "passive"))
      (node (ref "C13") (pin "1") (pinfunction "1_1") (pintype "passive"))
      (node (ref "C3") (pin "1") (pinfunction "1_1") (pintype "passive"))
      (node (ref "C4") (pin "1") (pinfunction "1_1") (pintype "passive"))
      (node (ref "C5") (pin "1") (pinfunction "1_1") (pintype "passive"))
      (node (ref "C6") (pin "1") (pinfunction "1_1") (pintype "passive"))
      (node (ref "C7") (pin "1") (pinfunction "1_1") (pintype "passive"))
      (node (ref "C8") (pin "1") (pinfunction "1_1") (pintype "passive"))
      (node (ref "C9") (pin "2") (pinfunction "2_2") (pintype "passive"))
      (node (ref "CN1") (pin "2") (pinfunction "GND_2") (pintype "passive"))
      (node (ref "CN1") (pin "3") (pinfunction "GND_3") (pintype "passive"))
      (node (ref "CN2") (pin "7") (pinfunction "7_7") (pintype "passive"))
      (node (ref "CN5") (pin "6") (pinfunction "6_6") (pintype "passive"))
      (node (ref "CN6") (pin "2") (pinfunction "2_2") (pintype "passive"))
      (node (ref "CN7") (pin "5") (pinfunction "GND_5") (pintype "power_in"))
      (node (ref "CN9") (pin "6") (pinfunction "6_6") (pintype "passive"))
      (node (ref "CN9") (pin "7") (pinfunction "7_7") (pintype "passive"))
      (node (ref "D2") (pin "2") (pinfunction "2_2") (pintype "passive"))
      (node (ref "FB3") (pin "2") (pinfunction "2_2") (pintype "passive"))
      (node (ref "IC1") (pin "1") (pinfunction "GND_1") (pintype "passive"))
      (node (ref "IC3") (pin "39") (pinfunction "D/AVSS_39") (pintype "power_in"))
      (node (ref "IC3") (pin "41") (pinfunction "GND_41") (pintype "power_in"))
      (node (ref "IC4") (pin "29") (pinfunction "GND_29") (pintype "power_in"))
      (node (ref "IC4") (pin "3") (pinfunction "GND_3") (pintype "power_in"))
      (node (ref "LED1") (pin "1") (pinfunction "1_1") (pintype "passive"))
      (node (ref "LED2") (pin "1") (pinfunction "1_1") (pintype "passive"))
      (node (ref "LED3") (pin "1") (pinfunction "1_1") (pintype "passive"))
      (node (ref "LED4") (pin "1") (pinfunction "1_1") (pintype "passive"))
      (node (ref "LED5") (pin "1") (pinfunction "1_1") (pintype "passive"))
      (node (ref "LED6") (pin "1") (pinfunction "1_1") (pintype "passive"))
      (node (ref "LED7") (pin "1") (pinfunction "1_1") (pintype "passive"))
      (node (ref "R14") (pin "2") (pinfunction "2_2") (pintype "passive"))
      (node (ref "R15") (pin "2") (pinfunction "2_2") (pintype "passive"))
      (node (ref "R3") (pin "2") (pinfunction "2_2") (pintype "passive"))
      (node (ref "SW1") (pin "2") (pinfunction "A1_2") (pintype "passive"))
      (node (ref "SW2") (pin "2") (pinfunction "A1_2") (pintype "passive"))
    )
    (net (code "53") (name "Net-(C4-Pad2)") (class "Default")
      (node (ref "C4") (pin "2") (pinfunction "2_2") (pintype "passive"))
      (node (ref "D4") (pin "2") (pinfunction "2_2") (pintype "passive"))
      (node (ref "IC1") (pin "2") (pinfunction "VOUT_2") (pintype "passive"))
      (node (ref "IC1") (pin "4") (pinfunction "VOUT_4") (pintype "passive"))
    )
    (net (code "54") (name "Net-(CN7-D+)") (class "Default")
      (node (ref "CN7") (pin "3") (pinfunction "D+_3") (pintype "bidirectional"))
      (node (ref "R2") (pin "2") (pinfunction "2_2") (pintype "passive"))
    )
    (net (code "55") (name "Net-(CN7-D-)") (class "Default")
      (node (ref "CN7") (pin "2") (pinfunction "D-_2") (pintype "bidirectional"))
      (node (ref "R1") (pin "2") (pinfunction "2_2") (pintype "passive"))
    )
    (net (code "56") (name "Net-(CN7-ID)") (class "Default")
      (node (ref "CN7") (pin "4") (pinfunction "ID_4") (pintype "input"))
      (node (ref "R3") (pin "1") (pinfunction "1_1") (pintype "passive"))
    )
    (net (code "57") (name "Net-(CN7-S1)") (class "Default")
      (node (ref "CN7") (pin "6") (pinfunction "S1_6") (pintype "power_in"))
      (node (ref "CN7") (pin "7") (pinfunction "S2_7") (pintype "power_in"))
      (node (ref "CN7") (pin "8") (pinfunction "S3_8") (pintype "power_in"))
      (node (ref "CN7") (pin "9") (pinfunction "S4_9") (pintype "power_in"))
      (node (ref "FB3") (pin "1") (pinfunction "1_1") (pintype "passive"))
    )
    (net (code "58") (name "Net-(D1-Pad2)") (class "Default")
      (node (ref "D1") (pin "2") (pinfunction "2_2") (pintype "passive"))
      (node (ref "F1") (pin "2") (pinfunction "2_2") (pintype "passive"))
    )
    (net (code "59") (name "Net-(IC3-AVCC)") (class "Default")
      (node (ref "C5") (pin "2") (pinfunction "2_2") (pintype "passive"))
      (node (ref "C6") (pin "2") (pinfunction "2_2") (pintype "passive"))
      (node (ref "FB1") (pin "2") (pinfunction "2_2") (pintype "passive"))
      (node (ref "IC3") (pin "1") (pinfunction "DVDD_1") (pintype "power_in"))
      (node (ref "IC3") (pin "40") (pinfunction "AVCC_40") (pintype "power_in"))
    )
    (net (code "60") (name "Net-(IC3-XIN{slash}P2.6{slash}CA6)") (class "Default")
      (node (ref "C7") (pin "2") (pinfunction "2_2") (pintype "passive"))
      (node (ref "IC3") (pin "2") (pinfunction "XIN/P2.6/CA6_2") (pintype "bidirectional"))
      (node (ref "X1") (pin "1") (pinfunction "1_1") (pintype "passive"))
    )
    (net (code "61") (name "Net-(IC3-XOUT{slash}P2.7{slash}CA7)") (class "Default")
      (node (ref "C8") (pin "2") (pinfunction "2_2") (pintype "passive"))
      (node (ref "IC3") (pin "3") (pinfunction "XOUT/P2.7/CA7_3") (pintype "bidirectional"))
      (node (ref "X1") (pin "2") (pinfunction "2_2") (pintype "passive"))
    )
    (net (code "62") (name "Net-(IC4-RST)") (class "Default")
      (node (ref "IC4") (pin "9") (pinfunction "RST_9") (pintype "bidirectional"))
      (node (ref "R4") (pin "1") (pinfunction "1_1") (pintype "passive"))
    )
    (net (code "63") (name "Net-(IC4-VDD)") (class "Default")
      (node (ref "C11") (pin "2") (pinfunction "2_2") (pintype "passive"))
      (node (ref "IC4") (pin "6") (pinfunction "VDD_6") (pintype "power_in"))
    )
    (net (code "64") (name "Net-(LED1-Pad2)") (class "Default")
      (node (ref "LED1") (pin "2") (pinfunction "2_2") (pintype "passive"))
      (node (ref "R7") (pin "1") (pinfunction "1_1") (pintype "passive"))
    )
    (net (code "65") (name "Net-(LED2-Pad2)") (class "Default")
      (node (ref "LED2") (pin "2") (pinfunction "2_2") (pintype "passive"))
      (node (ref "R8") (pin "1") (pinfunction "1_1") (pintype "passive"))
    )
    (net (code "66") (name "Net-(LED3-Pad2)") (class "Default")
      (node (ref "LED3") (pin "2") (pinfunction "2_2") (pintype "passive"))
      (node (ref "R9") (pin "1") (pinfunction "1_1") (pintype "passive"))
    )
    (net (code "67") (name "Net-(LED4-Pad2)") (class "Default")
      (node (ref "LED4") (pin "2") (pinfunction "2_2") (pintype "passive"))
      (node (ref "R10") (pin "1") (pinfunction "1_1") (pintype "passive"))
    )
    (net (code "68") (name "Net-(LED5-Pad2)") (class "Default")
      (node (ref "LED5") (pin "2") (pinfunction "2_2") (pintype "passive"))
      (node (ref "R11") (pin "1") (pinfunction "1_1") (pintype "passive"))
    )
    (net (code "69") (name "Net-(LED6-Pad2)") (class "Default")
      (node (ref "LED6") (pin "2") (pinfunction "2_2") (pintype "passive"))
      (node (ref "R12") (pin "1") (pinfunction "1_1") (pintype "passive"))
    )
    (net (code "70") (name "Net-(LED7-Pad2)") (class "Default")
      (node (ref "LED7") (pin "2") (pinfunction "2_2") (pintype "passive"))
      (node (ref "R13") (pin "1") (pinfunction "1_1") (pintype "passive"))
    )
    (net (code "71") (name "Net-(LED8-Pad1)") (class "Default")
      (node (ref "LED8") (pin "1") (pinfunction "1_1") (pintype "passive"))
      (node (ref "R15") (pin "1") (pinfunction "1_1") (pintype "passive"))
    )
    (net (code "72") (name "Net-(LED9-Pad2)") (class "Default")
      (node (ref "LED9") (pin "2") (pinfunction "2_2") (pintype "passive"))
      (node (ref "R16") (pin "1") (pinfunction "1_1") (pintype "passive"))
    )
    (net (code "73") (name "Net-(LED10-Pad2)") (class "Default")
      (node (ref "LED10") (pin "2") (pinfunction "2_2") (pintype "passive"))
      (node (ref "R17") (pin "1") (pinfunction "1_1") (pintype "passive"))
    )
    (net (code "74") (name "VIN") (class "Default")
      (node (ref "CN1") (pin "1") (pinfunction "+_1") (pintype "passive"))
      (node (ref "CN9") (pin "8") (pinfunction "8_8") (pintype "passive"))
      (node (ref "F1") (pin "1") (pinfunction "1_1") (pintype "passive"))
    )
    (net (code "75") (name "unconnected-(CN9-Pad1)") (class "Default")
      (node (ref "CN9") (pin "1") (pinfunction "1_1") (pintype "passive"))
    )
    (net (code "76") (name "unconnected-(IC4-CTS-Pad23)") (class "Default")
      (node (ref "IC4") (pin "23") (pinfunction "CTS_23") (pintype "input+no_connect"))
    )
    (net (code "77") (name "unconnected-(IC4-DCD-Pad1)") (class "Default")
      (node (ref "IC4") (pin "1") (pinfunction "DCD_1") (pintype "input+no_connect"))
    )
    (net (code "78") (name "unconnected-(IC4-DSR-Pad27)") (class "Default")
      (node (ref "IC4") (pin "27") (pinfunction "DSR_27") (pintype "input+no_connect"))
    )
    (net (code "79") (name "unconnected-(IC4-DTR-Pad28)") (class "Default")
      (node (ref "IC4") (pin "28") (pinfunction "DTR_28") (pintype "output+no_connect"))
    )
    (net (code "80") (name "unconnected-(IC4-NC-Pad10)") (class "Default")
      (node (ref "IC4") (pin "10") (pinfunction "NC_10") (pintype "passive+no_connect"))
    )
    (net (code "81") (name "unconnected-(IC4-NC-Pad13)") (class "Default")
      (node (ref "IC4") (pin "13") (pinfunction "NC_13") (pintype "passive+no_connect"))
    )
    (net (code "82") (name "unconnected-(IC4-NC-Pad14)") (class "Default")
      (node (ref "IC4") (pin "14") (pinfunction "NC_14") (pintype "passive+no_connect"))
    )
    (net (code "83") (name "unconnected-(IC4-NC-Pad15)") (class "Default")
      (node (ref "IC4") (pin "15") (pinfunction "NC_15") (pintype "passive+no_connect"))
    )
    (net (code "84") (name "unconnected-(IC4-NC-Pad16)") (class "Default")
      (node (ref "IC4") (pin "16") (pinfunction "NC_16") (pintype "passive+no_connect"))
    )
    (net (code "85") (name "unconnected-(IC4-NC-Pad17)") (class "Default")
      (node (ref "IC4") (pin "17") (pinfunction "NC_17") (pintype "passive+no_connect"))
    )
    (net (code "86") (name "unconnected-(IC4-NC-Pad18)") (class "Default")
      (node (ref "IC4") (pin "18") (pinfunction "NC_18") (pintype "passive+no_connect"))
    )
    (net (code "87") (name "unconnected-(IC4-NC-Pad19)") (class "Default")
      (node (ref "IC4") (pin "19") (pinfunction "NC_19") (pintype "passive+no_connect"))
    )
    (net (code "88") (name "unconnected-(IC4-NC-Pad20)") (class "Default")
      (node (ref "IC4") (pin "20") (pinfunction "NC_20") (pintype "passive+no_connect"))
    )
    (net (code "89") (name "unconnected-(IC4-NC-Pad21)") (class "Default")
      (node (ref "IC4") (pin "21") (pinfunction "NC_21") (pintype "passive+no_connect"))
    )
    (net (code "90") (name "unconnected-(IC4-NC-Pad22)") (class "Default")
      (node (ref "IC4") (pin "22") (pinfunction "NC_22") (pintype "passive+no_connect"))
    )
    (net (code "91") (name "unconnected-(IC4-RI-Pad2)") (class "Default")
      (node (ref "IC4") (pin "2") (pinfunction "RI_2") (pintype "input+no_connect"))
    )
    (net (code "92") (name "unconnected-(IC4-RTS-Pad24)") (class "Default")
      (node (ref "IC4") (pin "24") (pinfunction "RTS_24") (pintype "output+no_connect"))
    )
    (net (code "93") (name "unconnected-(IC4-SUSPEND-Pad12)") (class "Default")
      (node (ref "IC4") (pin "12") (pinfunction "SUSPEND_12") (pintype "output"))
    )
    (net (code "94") (name "unconnected-(IC4-~{SUSPEND}-Pad11)") (class "Default")
      (node (ref "IC4") (pin "11") (pinfunction "~{SUSPEND}_11") (pintype "output"))
    )
  )
)
